# schematic.net
KiCad netlist of a schematic drawn in EAGLE
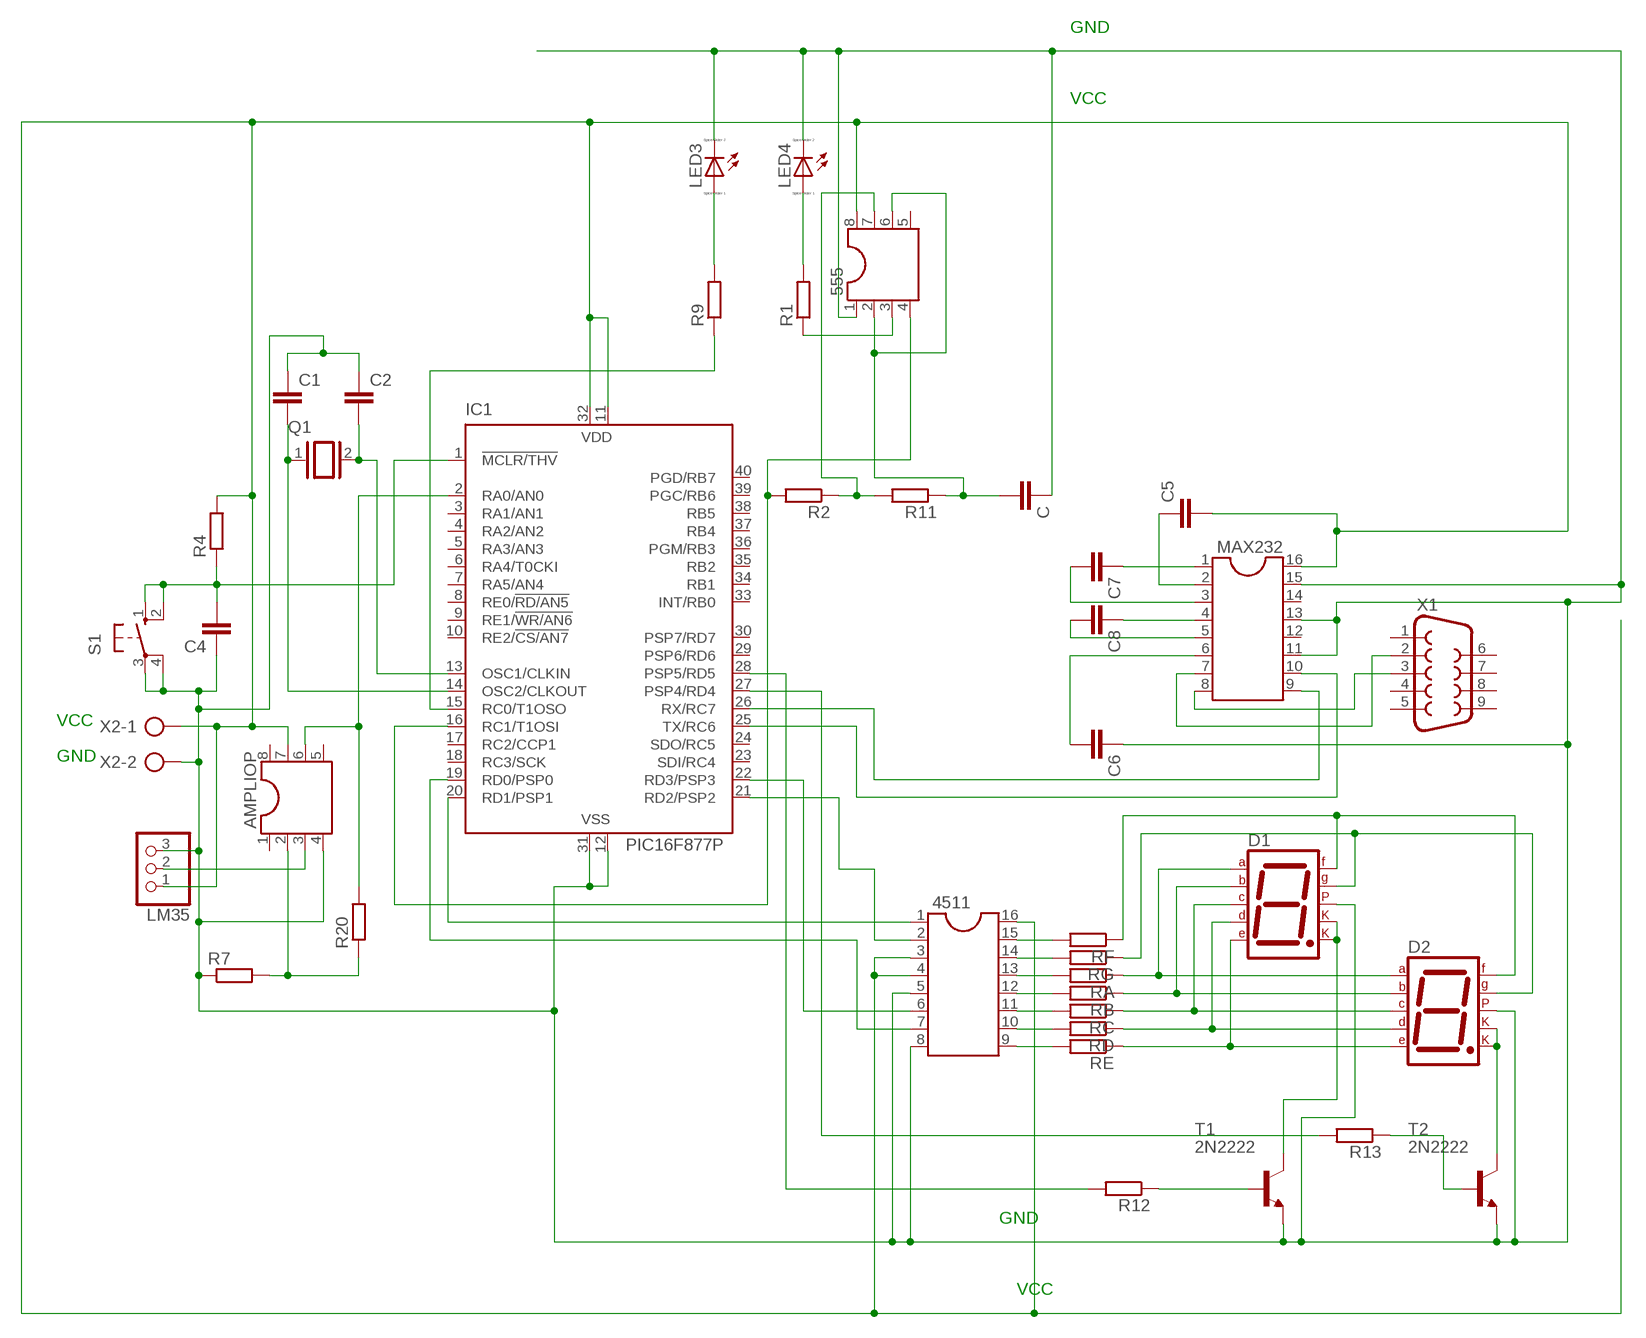
[diagram p0: schematic, sheet 1]

(export (version "E")
  (design (tool "Eeschema 10.0.6"))
  (components
    (comp (ref "555")
      (value "DIL8")
      (footprint "eagle-import:DIL08")
      (libsource (lib "eagle-import") (part "DIL8"))
    )
    (comp (ref "4511")
      (value "DIL16")
      (footprint "eagle-import:DIL16")
      (libsource (lib "eagle-import") (part "DIL16"))
    )
    (comp (ref "AMPLIOP")
      (value "DIL8")
      (footprint "eagle-import:DIL08")
      (libsource (lib "eagle-import") (part "DIL8"))
    )
    (comp (ref "C")
      (value "C-EU025-050X050")
      (footprint "eagle-import:C025-050X050")
      (libsource (lib "eagle-import") (part "C-EU025-050X050"))
    )
    (comp (ref "C1")
      (value "C-EU025-050X050")
      (footprint "eagle-import:C025-050X050")
      (libsource (lib "eagle-import") (part "C-EU025-050X050"))
    )
    (comp (ref "C2")
      (value "C-EU025-050X050")
      (footprint "eagle-import:C025-050X050")
      (libsource (lib "eagle-import") (part "C-EU025-050X050"))
    )
    (comp (ref "C4")
      (value "C-EU025-050X050")
      (footprint "eagle-import:C025-050X050")
      (libsource (lib "eagle-import") (part "C-EU025-050X050"))
    )
    (comp (ref "C5")
      (value "C-EU025-050X050")
      (footprint "eagle-import:C025-050X050")
      (libsource (lib "eagle-import") (part "C-EU025-050X050"))
    )
    (comp (ref "C6")
      (value "C-EU025-050X050")
      (footprint "eagle-import:C025-050X050")
      (libsource (lib "eagle-import") (part "C-EU025-050X050"))
    )
    (comp (ref "C7")
      (value "C-EU025-050X050")
      (footprint "eagle-import:C025-050X050")
      (libsource (lib "eagle-import") (part "C-EU025-050X050"))
    )
    (comp (ref "C8")
      (value "C-EU025-050X050")
      (footprint "eagle-import:C025-050X050")
      (libsource (lib "eagle-import") (part "C-EU025-050X050"))
    )
    (comp (ref "D1")
      (value "7SEG-CK")
      (footprint "eagle-import:7SEG-13")
      (libsource (lib "eagle-import") (part "7SEG-CK"))
    )
    (comp (ref "D2")
      (value "7SEG-CK")
      (footprint "eagle-import:7SEG-13")
      (libsource (lib "eagle-import") (part "7SEG-CK"))
    )
    (comp (ref "IC1")
      (value "PIC16F877P")
      (footprint "eagle-import:DIL40")
      (fields (field (name "MF") "MICROCHIP") (field (name "MPN") "PIC16F877-04/P"))
      (libsource (lib "eagle-import") (part "PIC16F87P7"))
    )
    (comp (ref "LED3")
      (value "LED_ELD260")
      (footprint "eagle-import:LED_LD260")
      (libsource (lib "eagle-import") (part "LED_ELD260"))
    )
    (comp (ref "LED4")
      (value "LED_ELD260")
      (footprint "eagle-import:LED_LD260")
      (libsource (lib "eagle-import") (part "LED_ELD260"))
    )
    (comp (ref "LM35")
      (value "PINHD-1X3")
      (footprint "eagle-import:1X03")
      (libsource (lib "eagle-import") (part "PINHD-1X3"))
    )
    (comp (ref "MAX232")
      (value "DIL16")
      (footprint "eagle-import:DIL16")
      (libsource (lib "eagle-import") (part "DIL16"))
    )
    (comp (ref "Q1")
      (value "XTAL/S")
      (footprint "eagle-import:QS")
      (libsource (lib "eagle-import") (part "XTAL/S"))
    )
    (comp (ref "R1")
      (value "R-EU_0204/7")
      (footprint "eagle-import:0204_7")
      (libsource (lib "eagle-import") (part "R-EU_0204/7"))
    )
    (comp (ref "R2")
      (value "R-EU_0204/7")
      (footprint "eagle-import:0204_7")
      (libsource (lib "eagle-import") (part "R-EU_0204/7"))
    )
    (comp (ref "R4")
      (value "R-EU_0204/7")
      (footprint "eagle-import:0204_7")
      (libsource (lib "eagle-import") (part "R-EU_0204/7"))
    )
    (comp (ref "R7")
      (value "R-EU_0204/7")
      (footprint "eagle-import:0204_7")
      (libsource (lib "eagle-import") (part "R-EU_0204/7"))
    )
    (comp (ref "R9")
      (value "R-EU_0204/7")
      (footprint "eagle-import:0204_7")
      (libsource (lib "eagle-import") (part "R-EU_0204/7"))
    )
    (comp (ref "R11")
      (value "R-EU_0204/7")
      (footprint "eagle-import:0204_7")
      (libsource (lib "eagle-import") (part "R-EU_0204/7"))
    )
    (comp (ref "R12")
      (value "R-EU_0204/7")
      (footprint "eagle-import:0204_7")
      (libsource (lib "eagle-import") (part "R-EU_0204/7"))
    )
    (comp (ref "R13")
      (value "R-EU_0204/7")
      (footprint "eagle-import:0204_7")
      (libsource (lib "eagle-import") (part "R-EU_0204/7"))
    )
    (comp (ref "R20")
      (value "R-EU_0204/7")
      (footprint "eagle-import:0204_7")
      (libsource (lib "eagle-import") (part "R-EU_0204/7"))
    )
    (comp (ref "RA")
      (value "R-EU_0204/7")
      (footprint "eagle-import:0204_7")
      (libsource (lib "eagle-import") (part "R-EU_0204/7"))
    )
    (comp (ref "RB")
      (value "R-EU_0204/7")
      (footprint "eagle-import:0204_7")
      (libsource (lib "eagle-import") (part "R-EU_0204/7"))
    )
    (comp (ref "RC")
      (value "R-EU_0204/7")
      (footprint "eagle-import:0204_7")
      (libsource (lib "eagle-import") (part "R-EU_0204/7"))
    )
    (comp (ref "RD")
      (value "R-EU_0204/7")
      (footprint "eagle-import:0204_7")
      (libsource (lib "eagle-import") (part "R-EU_0204/7"))
    )
    (comp (ref "RE")
      (value "R-EU_0204/7")
      (footprint "eagle-import:0204_7")
      (libsource (lib "eagle-import") (part "R-EU_0204/7"))
    )
    (comp (ref "RF")
      (value "R-EU_0204/7")
      (footprint "eagle-import:0204_7")
      (libsource (lib "eagle-import") (part "R-EU_0204/7"))
    )
    (comp (ref "RG")
      (value "R-EU_0204/7")
      (footprint "eagle-import:0204_7")
      (libsource (lib "eagle-import") (part "R-EU_0204/7"))
    )
    (comp (ref "S1")
      (value "10-XX")
      (footprint "eagle-import:B3F-10XX")
      (fields (field (name "MPN") "B3F-1000"))
      (libsource (lib "eagle-import") (part "10-XX"))
    )
    (comp (ref "T1")
      (value "2N2222")
      (footprint "eagle-import:TO18")
      (libsource (lib "eagle-import") (part "2N2222"))
    )
    (comp (ref "T2")
      (value "2N2222")
      (footprint "eagle-import:TO18")
      (libsource (lib "eagle-import") (part "2N2222"))
    )
    (comp (ref "X1")
      (value "F09V")
      (footprint "eagle-import:F09V")
      (libsource (lib "eagle-import") (part "F09V"))
    )
    (comp (ref "X2")
      (value "AK300/2")
      (footprint "eagle-import:AK300_2")
      (libsource (lib "eagle-import") (part "AK300/2"))
    )
  )
  (nets
    (net (code "1") (name "Net-(555-Pad2)") (class "Default")
      (node (ref "555") (pin "2") (pinfunction "2_2") (pintype "passive"))
      (node (ref "555") (pin "6") (pinfunction "6_6") (pintype "passive"))
      (node (ref "C") (pin "2") (pinfunction "2_2") (pintype "passive"))
      (node (ref "R11") (pin "1") (pinfunction "1_1") (pintype "passive"))
    )
    (net (code "2") (name "Net-(555-Pad3)") (class "Default")
      (node (ref "555") (pin "3") (pinfunction "3_3") (pintype "passive"))
      (node (ref "R1") (pin "1") (pinfunction "1_1") (pintype "passive"))
    )
    (net (code "3") (name "Net-(555-Pad7)") (class "Default")
      (node (ref "555") (pin "7") (pinfunction "7_7") (pintype "passive"))
      (node (ref "R11") (pin "2") (pinfunction "2_2") (pintype "passive"))
      (node (ref "R2") (pin "1") (pinfunction "1_1") (pintype "passive"))
    )
    (net (code "4") (name "Net-(4511-Pad9)") (class "Default")
      (node (ref "4511") (pin "9") (pinfunction "9_9") (pintype "passive"))
      (node (ref "RE") (pin "2") (pinfunction "2_2") (pintype "passive"))
    )
    (net (code "5") (name "Net-(4511-Pad10)") (class "Default")
      (node (ref "4511") (pin "10") (pinfunction "10_10") (pintype "passive"))
      (node (ref "RD") (pin "2") (pinfunction "2_2") (pintype "passive"))
    )
    (net (code "6") (name "Net-(4511-Pad11)") (class "Default")
      (node (ref "4511") (pin "11") (pinfunction "11_11") (pintype "passive"))
      (node (ref "RC") (pin "2") (pinfunction "2_2") (pintype "passive"))
    )
    (net (code "7") (name "Net-(4511-Pad12)") (class "Default")
      (node (ref "4511") (pin "12") (pinfunction "12_12") (pintype "passive"))
      (node (ref "RB") (pin "2") (pinfunction "2_2") (pintype "passive"))
    )
    (net (code "8") (name "Net-(4511-Pad13)") (class "Default")
      (node (ref "4511") (pin "13") (pinfunction "13_13") (pintype "passive"))
      (node (ref "RA") (pin "2") (pinfunction "2_2") (pintype "passive"))
    )
    (net (code "9") (name "Net-(4511-Pad14)") (class "Default")
      (node (ref "4511") (pin "14") (pinfunction "14_14") (pintype "passive"))
      (node (ref "RG") (pin "2") (pinfunction "2_2") (pintype "passive"))
    )
    (net (code "10") (name "Net-(4511-Pad15)") (class "Default")
      (node (ref "4511") (pin "15") (pinfunction "15_15") (pintype "passive"))
      (node (ref "RF") (pin "2") (pinfunction "2_2") (pintype "passive"))
    )
    (net (code "11") (name "Net-(AMPLIOP-Pad2)") (class "Default")
      (node (ref "AMPLIOP") (pin "2") (pinfunction "2_2") (pintype "passive"))
      (node (ref "R20") (pin "1") (pinfunction "1_1") (pintype "passive"))
      (node (ref "R7") (pin "2") (pinfunction "2_2") (pintype "passive"))
    )
    (net (code "12") (name "Net-(AMPLIOP-Pad3)") (class "Default")
      (node (ref "AMPLIOP") (pin "3") (pinfunction "3_3") (pintype "passive"))
      (node (ref "LM35") (pin "2") (pinfunction "2_2") (pintype "passive"))
    )
    (net (code "13") (name "Net-(C5-Pad1)") (class "Default")
      (node (ref "C5") (pin "1") (pinfunction "1_1") (pintype "passive"))
      (node (ref "MAX232") (pin "2") (pinfunction "2_2") (pintype "passive"))
    )
    (net (code "14") (name "Net-(C6-Pad2)") (class "Default")
      (node (ref "C6") (pin "2") (pinfunction "2_2") (pintype "passive"))
      (node (ref "MAX232") (pin "6") (pinfunction "6_6") (pintype "passive"))
    )
    (net (code "15") (name "Net-(C7-Pad1)") (class "Default")
      (node (ref "C7") (pin "1") (pinfunction "1_1") (pintype "passive"))
      (node (ref "MAX232") (pin "1") (pinfunction "1_1") (pintype "passive"))
    )
    (net (code "16") (name "Net-(C7-Pad2)") (class "Default")
      (node (ref "C7") (pin "2") (pinfunction "2_2") (pintype "passive"))
      (node (ref "MAX232") (pin "3") (pinfunction "3_3") (pintype "passive"))
    )
    (net (code "17") (name "Net-(C8-Pad1)") (class "Default")
      (node (ref "C8") (pin "1") (pinfunction "1_1") (pintype "passive"))
      (node (ref "MAX232") (pin "4") (pinfunction "4_4") (pintype "passive"))
    )
    (net (code "18") (name "Net-(C8-Pad2)") (class "Default")
      (node (ref "C8") (pin "2") (pinfunction "2_2") (pintype "passive"))
      (node (ref "MAX232") (pin "5") (pinfunction "5_5") (pintype "passive"))
    )
    (net (code "19") (name "Net-(D1-A)") (class "Default")
      (node (ref "D1") (pin "7") (pinfunction "A_7") (pintype "passive"))
      (node (ref "D2") (pin "7") (pinfunction "A_7") (pintype "passive"))
      (node (ref "RA") (pin "1") (pinfunction "1_1") (pintype "passive"))
    )
    (net (code "20") (name "Net-(D1-B)") (class "Default")
      (node (ref "D1") (pin "6") (pinfunction "B_6") (pintype "passive"))
      (node (ref "D2") (pin "6") (pinfunction "B_6") (pintype "passive"))
      (node (ref "RB") (pin "1") (pinfunction "1_1") (pintype "passive"))
    )
    (net (code "21") (name "Net-(D1-C)") (class "Default")
      (node (ref "D1") (pin "4") (pinfunction "C_4") (pintype "passive"))
      (node (ref "D2") (pin "4") (pinfunction "C_4") (pintype "passive"))
      (node (ref "RC") (pin "1") (pinfunction "1_1") (pintype "passive"))
    )
    (net (code "22") (name "Net-(D1-CK1)") (class "Default")
      (node (ref "D1") (pin "3") (pinfunction "CK1_3") (pintype "passive"))
      (node (ref "D1") (pin "8") (pinfunction "CK2_8") (pintype "passive"))
      (node (ref "T1") (pin "3") (pinfunction "C_3") (pintype "passive"))
    )
    (net (code "23") (name "Net-(D1-D)") (class "Default")
      (node (ref "D1") (pin "2") (pinfunction "D_2") (pintype "passive"))
      (node (ref "D2") (pin "2") (pinfunction "D_2") (pintype "passive"))
      (node (ref "RD") (pin "1") (pinfunction "1_1") (pintype "passive"))
    )
    (net (code "24") (name "Net-(D1-DP)") (class "Default")
      (node (ref "4511") (pin "5") (pinfunction "5_5") (pintype "passive"))
      (node (ref "4511") (pin "8") (pinfunction "8_8") (pintype "passive"))
      (node (ref "555") (pin "1") (pinfunction "1_1") (pintype "passive"))
      (node (ref "AMPLIOP") (pin "4") (pinfunction "4_4") (pintype "passive"))
      (node (ref "C") (pin "1") (pinfunction "1_1") (pintype "passive"))
      (node (ref "C1") (pin "1") (pinfunction "1_1") (pintype "passive"))
      (node (ref "C2") (pin "1") (pinfunction "1_1") (pintype "passive"))
      (node (ref "C4") (pin "1") (pinfunction "1_1") (pintype "passive"))
      (node (ref "C6") (pin "1") (pinfunction "1_1") (pintype "passive"))
      (node (ref "D1") (pin "5") (pinfunction "DP_5") (pintype "passive"))
      (node (ref "D2") (pin "5") (pinfunction "DP_5") (pintype "passive"))
      (node (ref "IC1") (pin "12") (pinfunction "VSS_12") (pintype "power_in"))
      (node (ref "IC1") (pin "31") (pinfunction "VSS_31") (pintype "power_in"))
      (node (ref "LED3") (pin "K") (pinfunction "C_K") (pintype "passive"))
      (node (ref "LED4") (pin "K") (pinfunction "C_K") (pintype "passive"))
      (node (ref "LM35") (pin "3") (pinfunction "3_3") (pintype "passive"))
      (node (ref "MAX232") (pin "11") (pinfunction "11_11") (pintype "passive"))
      (node (ref "MAX232") (pin "13") (pinfunction "13_13") (pintype "passive"))
      (node (ref "MAX232") (pin "15") (pinfunction "15_15") (pintype "passive"))
      (node (ref "R7") (pin "1") (pinfunction "1_1") (pintype "passive"))
      (node (ref "S1") (pin "3") (pinfunction "P_3") (pintype "passive"))
      (node (ref "S1") (pin "4") (pinfunction "P1_4") (pintype "passive"))
      (node (ref "T1") (pin "1") (pinfunction "E_1") (pintype "passive"))
      (node (ref "T2") (pin "1") (pinfunction "E_1") (pintype "passive"))
      (node (ref "X2") (pin "2") (pinfunction "KL_2") (pintype "passive"))
    )
    (net (code "25") (name "Net-(D1-E)") (class "Default")
      (node (ref "D1") (pin "1") (pinfunction "E_1") (pintype "passive"))
      (node (ref "D2") (pin "1") (pinfunction "E_1") (pintype "passive"))
      (node (ref "RE") (pin "1") (pinfunction "1_1") (pintype "passive"))
    )
    (net (code "26") (name "Net-(D1-F)") (class "Default")
      (node (ref "D1") (pin "9") (pinfunction "F_9") (pintype "passive"))
      (node (ref "D2") (pin "9") (pinfunction "F_9") (pintype "passive"))
      (node (ref "RF") (pin "1") (pinfunction "1_1") (pintype "passive"))
    )
    (net (code "27") (name "Net-(D1-G)") (class "Default")
      (node (ref "D1") (pin "10") (pinfunction "G_10") (pintype "passive"))
      (node (ref "D2") (pin "10") (pinfunction "G_10") (pintype "passive"))
      (node (ref "RG") (pin "1") (pinfunction "1_1") (pintype "passive"))
    )
    (net (code "28") (name "Net-(D2-CK1)") (class "Default")
      (node (ref "D2") (pin "3") (pinfunction "CK1_3") (pintype "passive"))
      (node (ref "D2") (pin "8") (pinfunction "CK2_8") (pintype "passive"))
      (node (ref "T2") (pin "3") (pinfunction "C_3") (pintype "passive"))
    )
    (net (code "29") (name "Net-(IC1-OSC1{slash}CLKIN)") (class "Default")
      (node (ref "C2") (pin "2") (pinfunction "2_2") (pintype "passive"))
      (node (ref "IC1") (pin "13") (pinfunction "OSC1/CLKIN_13") (pintype "input"))
      (node (ref "Q1") (pin "2") (pinfunction "2_2") (pintype "passive"))
    )
    (net (code "30") (name "Net-(IC1-OSC2{slash}CLKOUT)") (class "Default")
      (node (ref "C1") (pin "2") (pinfunction "2_2") (pintype "passive"))
      (node (ref "IC1") (pin "14") (pinfunction "OSC2/CLKOUT_14") (pintype "output"))
      (node (ref "Q1") (pin "1") (pinfunction "1_1") (pintype "passive"))
    )
    (net (code "31") (name "Net-(IC1-PSP4{slash}RD4)") (class "Default")
      (node (ref "IC1") (pin "27") (pinfunction "PSP4/RD4_27") (pintype "bidirectional"))
      (node (ref "R13") (pin "2") (pinfunction "2_2") (pintype "passive"))
    )
    (net (code "32") (name "Net-(IC1-PSP5{slash}RD5)") (class "Default")
      (node (ref "IC1") (pin "28") (pinfunction "PSP5/RD5_28") (pintype "bidirectional"))
      (node (ref "R12") (pin "2") (pinfunction "2_2") (pintype "passive"))
    )
    (net (code "33") (name "Net-(IC1-RA0{slash}AN0)") (class "Default")
      (node (ref "AMPLIOP") (pin "6") (pinfunction "6_6") (pintype "passive"))
      (node (ref "IC1") (pin "2") (pinfunction "RA0/AN0_2") (pintype "bidirectional"))
      (node (ref "R20") (pin "2") (pinfunction "2_2") (pintype "passive"))
    )
    (net (code "34") (name "Net-(IC1-RC0{slash}T1OSO)") (class "Default")
      (node (ref "IC1") (pin "15") (pinfunction "RC0/T1OSO_15") (pintype "bidirectional"))
      (node (ref "R9") (pin "1") (pinfunction "1_1") (pintype "passive"))
    )
    (net (code "35") (name "Net-(IC1-RC1{slash}T1OSI)") (class "Default")
      (node (ref "555") (pin "4") (pinfunction "4_4") (pintype "passive"))
      (node (ref "IC1") (pin "16") (pinfunction "RC1/T1OSI_16") (pintype "bidirectional"))
      (node (ref "R2") (pin "2") (pinfunction "2_2") (pintype "passive"))
    )
    (net (code "36") (name "Net-(IC1-RD0{slash}PSP0)") (class "Default")
      (node (ref "4511") (pin "7") (pinfunction "7_7") (pintype "passive"))
      (node (ref "IC1") (pin "19") (pinfunction "RD0/PSP0_19") (pintype "bidirectional"))
    )
    (net (code "37") (name "Net-(IC1-RD1{slash}PSP1)") (class "Default")
      (node (ref "4511") (pin "1") (pinfunction "1_1") (pintype "passive"))
      (node (ref "IC1") (pin "20") (pinfunction "RD1/PSP1_20") (pintype "bidirectional"))
    )
    (net (code "38") (name "Net-(IC1-RD2{slash}PSP2)") (class "Default")
      (node (ref "4511") (pin "2") (pinfunction "2_2") (pintype "passive"))
      (node (ref "IC1") (pin "21") (pinfunction "RD2/PSP2_21") (pintype "bidirectional"))
    )
    (net (code "39") (name "Net-(IC1-RD3{slash}PSP3)") (class "Default")
      (node (ref "4511") (pin "6") (pinfunction "6_6") (pintype "passive"))
      (node (ref "IC1") (pin "22") (pinfunction "RD3/PSP3_22") (pintype "bidirectional"))
    )
    (net (code "40") (name "Net-(IC1-RX{slash}RC7)") (class "Default")
      (node (ref "IC1") (pin "26") (pinfunction "RX/RC7_26") (pintype "bidirectional"))
      (node (ref "MAX232") (pin "9") (pinfunction "9_9") (pintype "passive"))
    )
    (net (code "41") (name "Net-(IC1-TX{slash}RC6)") (class "Default")
      (node (ref "IC1") (pin "25") (pinfunction "TX/RC6_25") (pintype "bidirectional"))
      (node (ref "MAX232") (pin "10") (pinfunction "10_10") (pintype "passive"))
    )
    (net (code "42") (name "Net-(IC1-~{MCLR{slash}THV})") (class "Default")
      (node (ref "C4") (pin "2") (pinfunction "2_2") (pintype "passive"))
      (node (ref "IC1") (pin "1") (pinfunction "~{MCLR/THV}_1") (pintype "input"))
      (node (ref "R4") (pin "1") (pinfunction "1_1") (pintype "passive"))
      (node (ref "S1") (pin "1") (pinfunction "S_1") (pintype "passive"))
      (node (ref "S1") (pin "2") (pinfunction "S1_2") (pintype "passive"))
    )
    (net (code "43") (name "Net-(LED3-PadA)") (class "Default")
      (node (ref "LED3") (pin "A") (pinfunction "A_A") (pintype "passive"))
      (node (ref "R9") (pin "2") (pinfunction "2_2") (pintype "passive"))
    )
    (net (code "44") (name "Net-(LED4-PadA)") (class "Default")
      (node (ref "LED4") (pin "A") (pinfunction "A_A") (pintype "passive"))
      (node (ref "R1") (pin "2") (pinfunction "2_2") (pintype "passive"))
    )
    (net (code "45") (name "Net-(MAX232-Pad7)") (class "Default")
      (node (ref "MAX232") (pin "7") (pinfunction "7_7") (pintype "passive"))
      (node (ref "X1") (pin "2") (pinfunction "2_2") (pintype "passive"))
    )
    (net (code "46") (name "Net-(MAX232-Pad8)") (class "Default")
      (node (ref "MAX232") (pin "8") (pinfunction "8_8") (pintype "passive"))
      (node (ref "X1") (pin "3") (pinfunction "3_3") (pintype "passive"))
    )
    (net (code "47") (name "Net-(T1-B)") (class "Default")
      (node (ref "R12") (pin "1") (pinfunction "1_1") (pintype "passive"))
      (node (ref "T1") (pin "2") (pinfunction "B_2") (pintype "passive"))
    )
    (net (code "48") (name "Net-(T2-B)") (class "Default")
      (node (ref "R13") (pin "1") (pinfunction "1_1") (pintype "passive"))
      (node (ref "T2") (pin "2") (pinfunction "B_2") (pintype "passive"))
    )
    (net (code "49") (name "Net-(X2A-KL)") (class "Default")
      (node (ref "4511") (pin "16") (pinfunction "16_16") (pintype "passive"))
      (node (ref "4511") (pin "3") (pinfunction "3_3") (pintype "passive"))
      (node (ref "4511") (pin "4") (pinfunction "4_4") (pintype "passive"))
      (node (ref "555") (pin "8") (pinfunction "8_8") (pintype "passive"))
      (node (ref "AMPLIOP") (pin "7") (pinfunction "7_7") (pintype "passive"))
      (node (ref "C5") (pin "2") (pinfunction "2_2") (pintype "passive"))
      (node (ref "IC1") (pin "11") (pinfunction "VDD_11") (pintype "power_in"))
      (node (ref "IC1") (pin "32") (pinfunction "VDD_32") (pintype "power_in"))
      (node (ref "LM35") (pin "1") (pinfunction "1_1") (pintype "passive"))
      (node (ref "MAX232") (pin "16") (pinfunction "16_16") (pintype "passive"))
      (node (ref "R4") (pin "2") (pinfunction "2_2") (pintype "passive"))
      (node (ref "X2") (pin "1") (pinfunction "KL_1") (pintype "passive"))
    )
    (net (code "50") (name "unconnected-(555-Pad5)") (class "Default")
      (node (ref "555") (pin "5") (pinfunction "5_5") (pintype "passive"))
    )
    (net (code "51") (name "unconnected-(AMPLIOP-Pad1)") (class "Default")
      (node (ref "AMPLIOP") (pin "1") (pinfunction "1_1") (pintype "passive"))
    )
    (net (code "52") (name "unconnected-(AMPLIOP-Pad5)") (class "Default")
      (node (ref "AMPLIOP") (pin "5") (pinfunction "5_5") (pintype "passive"))
    )
    (net (code "53") (name "unconnected-(AMPLIOP-Pad8)") (class "Default")
      (node (ref "AMPLIOP") (pin "8") (pinfunction "8_8") (pintype "passive"))
    )
    (net (code "54") (name "unconnected-(IC1-INT{slash}RB0-Pad33)") (class "Default")
      (node (ref "IC1") (pin "33") (pinfunction "INT/RB0_33") (pintype "bidirectional"))
    )
    (net (code "55") (name "unconnected-(IC1-PGC{slash}RB6-Pad39)") (class "Default")
      (node (ref "IC1") (pin "39") (pinfunction "PGC/RB6_39") (pintype "bidirectional"))
    )
    (net (code "56") (name "unconnected-(IC1-PGD{slash}RB7-Pad40)") (class "Default")
      (node (ref "IC1") (pin "40") (pinfunction "PGD/RB7_40") (pintype "bidirectional"))
    )
    (net (code "57") (name "unconnected-(IC1-PGM{slash}RB3-Pad36)") (class "Default")
      (node (ref "IC1") (pin "36") (pinfunction "PGM/RB3_36") (pintype "bidirectional"))
    )
    (net (code "58") (name "unconnected-(IC1-PSP6{slash}RD6-Pad29)") (class "Default")
      (node (ref "IC1") (pin "29") (pinfunction "PSP6/RD6_29") (pintype "bidirectional"))
    )
    (net (code "59") (name "unconnected-(IC1-PSP7{slash}RD7-Pad30)") (class "Default")
      (node (ref "IC1") (pin "30") (pinfunction "PSP7/RD7_30") (pintype "bidirectional"))
    )
    (net (code "60") (name "unconnected-(IC1-RA1{slash}AN1-Pad3)") (class "Default")
      (node (ref "IC1") (pin "3") (pinfunction "RA1/AN1_3") (pintype "bidirectional"))
    )
    (net (code "61") (name "unconnected-(IC1-RA2{slash}AN2-Pad4)") (class "Default")
      (node (ref "IC1") (pin "4") (pinfunction "RA2/AN2_4") (pintype "bidirectional"))
    )
    (net (code "62") (name "unconnected-(IC1-RA3{slash}AN3-Pad5)") (class "Default")
      (node (ref "IC1") (pin "5") (pinfunction "RA3/AN3_5") (pintype "bidirectional"))
    )
    (net (code "63") (name "unconnected-(IC1-RA4{slash}T0CKI-Pad6)") (class "Default")
      (node (ref "IC1") (pin "6") (pinfunction "RA4/T0CKI_6") (pintype "bidirectional"))
    )
    (net (code "64") (name "unconnected-(IC1-RA5{slash}AN4-Pad7)") (class "Default")
      (node (ref "IC1") (pin "7") (pinfunction "RA5/AN4_7") (pintype "bidirectional"))
    )
    (net (code "65") (name "unconnected-(IC1-RB1-Pad34)") (class "Default")
      (node (ref "IC1") (pin "34") (pinfunction "RB1_34") (pintype "bidirectional"))
    )
    (net (code "66") (name "unconnected-(IC1-RB2-Pad35)") (class "Default")
      (node (ref "IC1") (pin "35") (pinfunction "RB2_35") (pintype "bidirectional"))
    )
    (net (code "67") (name "unconnected-(IC1-RB4-Pad37)") (class "Default")
      (node (ref "IC1") (pin "37") (pinfunction "RB4_37") (pintype "bidirectional"))
    )
    (net (code "68") (name "unconnected-(IC1-RB5-Pad38)") (class "Default")
      (node (ref "IC1") (pin "38") (pinfunction "RB5_38") (pintype "bidirectional"))
    )
    (net (code "69") (name "unconnected-(IC1-RC2{slash}CCP1-Pad17)") (class "Default")
      (node (ref "IC1") (pin "17") (pinfunction "RC2/CCP1_17") (pintype "bidirectional"))
    )
    (net (code "70") (name "unconnected-(IC1-RC3{slash}SCK-Pad18)") (class "Default")
      (node (ref "IC1") (pin "18") (pinfunction "RC3/SCK_18") (pintype "bidirectional"))
    )
    (net (code "71") (name "unconnected-(IC1-RE0{slash}~{RD{slash}AN5}-Pad8)") (class "Default")
      (node (ref "IC1") (pin "8") (pinfunction "RE0/~{RD/AN5}_8") (pintype "bidirectional"))
    )
    (net (code "72") (name "unconnected-(IC1-RE1{slash}~{WR{slash}AN6}-Pad9)") (class "Default")
      (node (ref "IC1") (pin "9") (pinfunction "RE1/~{WR/AN6}_9") (pintype "bidirectional"))
    )
    (net (code "73") (name "unconnected-(IC1-RE2{slash}~{CS{slash}AN7}-Pad10)") (class "Default")
      (node (ref "IC1") (pin "10") (pinfunction "RE2/~{CS/AN7}_10") (pintype "bidirectional"))
    )
    (net (code "74") (name "unconnected-(IC1-SDI{slash}RC4-Pad23)") (class "Default")
      (node (ref "IC1") (pin "23") (pinfunction "SDI/RC4_23") (pintype "bidirectional"))
    )
    (net (code "75") (name "unconnected-(IC1-SDO{slash}RC5-Pad24)") (class "Default")
      (node (ref "IC1") (pin "24") (pinfunction "SDO/RC5_24") (pintype "bidirectional"))
    )
    (net (code "76") (name "unconnected-(MAX232-Pad12)") (class "Default")
      (node (ref "MAX232") (pin "12") (pinfunction "12_12") (pintype "passive"))
    )
    (net (code "77") (name "unconnected-(MAX232-Pad14)") (class "Default")
      (node (ref "MAX232") (pin "14") (pinfunction "14_14") (pintype "passive"))
    )
    (net (code "78") (name "unconnected-(X1-Pad1)") (class "Default")
      (node (ref "X1") (pin "1") (pinfunction "1_1") (pintype "passive"))
    )
    (net (code "79") (name "unconnected-(X1-Pad4)") (class "Default")
      (node (ref "X1") (pin "4") (pinfunction "4_4") (pintype "passive"))
    )
    (net (code "80") (name "unconnected-(X1-Pad5)") (class "Default")
      (node (ref "X1") (pin "5") (pinfunction "5_5") (pintype "passive"))
    )
    (net (code "81") (name "unconnected-(X1-Pad6)") (class "Default")
      (node (ref "X1") (pin "6") (pinfunction "6_6") (pintype "passive"))
    )
    (net (code "82") (name "unconnected-(X1-Pad7)") (class "Default")
      (node (ref "X1") (pin "7") (pinfunction "7_7") (pintype "passive"))
    )
    (net (code "83") (name "unconnected-(X1-Pad8)") (class "Default")
      (node (ref "X1") (pin "8") (pinfunction "8_8") (pintype "passive"))
    )
    (net (code "84") (name "unconnected-(X1-Pad9)") (class "Default")
      (node (ref "X1") (pin "9") (pinfunction "9_9") (pintype "passive"))
    )
  )
)
